# kulgurpowerproto2.net
KiCad netlist of a schematic drawn in EAGLE
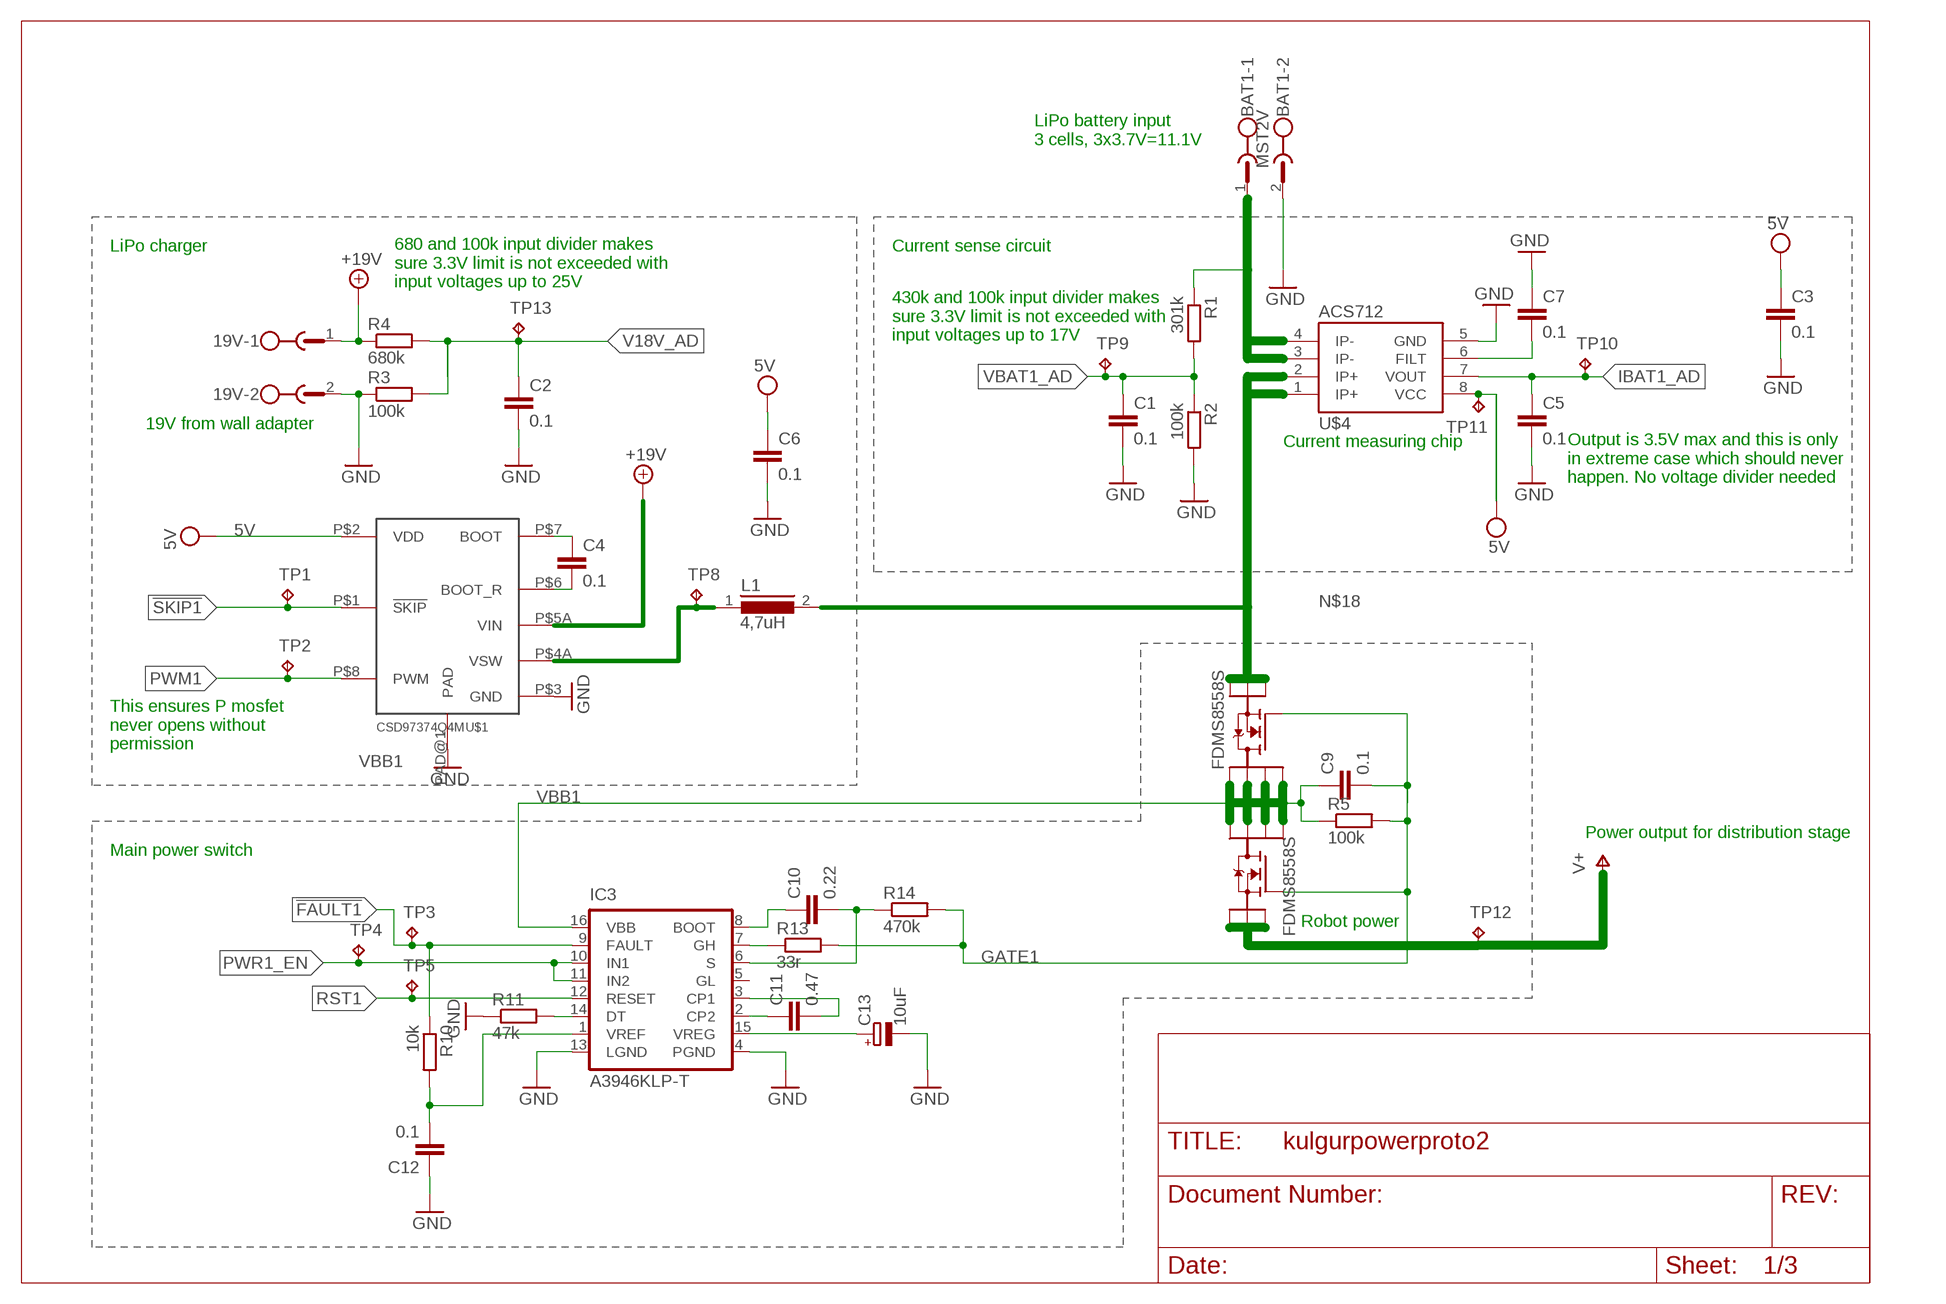
[diagram p0: schematic, sheet 1]
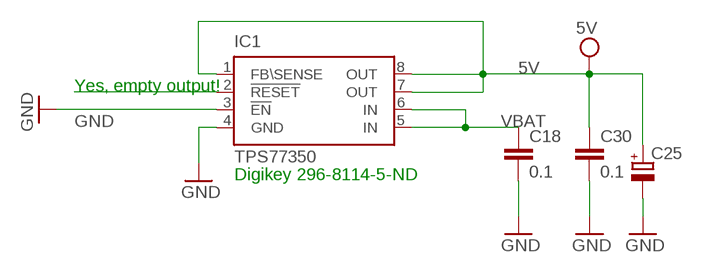
[diagram p1: schematic, sheet 2]
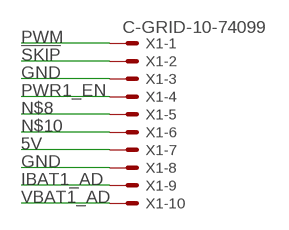
[diagram p2: schematic, sheet 3]

(export (version "E")
  (design (tool "Eeschema 10.0.6"))
  (components
    (comp (ref "C18")
      (value "0.1")
      (footprint "eagle-import:0603-CAP")
      (libsource (lib "eagle-import") (part "CAP0603-CAP"))
    )
    (comp (ref "C25")
      (value "CPOL-EUD/7343-31R")
      (footprint "eagle-import:D_7343-31R")
      (libsource (lib "eagle-import") (part "CPOL-EUD/7343-31R"))
    )
    (comp (ref "C30")
      (value "0.1")
      (footprint "eagle-import:0603-CAP")
      (libsource (lib "eagle-import") (part "CAP0603-CAP"))
    )
    (comp (ref "IC1")
      (value "TPS77350")
      (footprint "eagle-import:MSOP8")
      (libsource (lib "eagle-import") (part "TPS773"))
    )
    (comp (ref "X1")
      (value "C-GRID-10-74099")
      (footprint "eagle-import:74099-10")
      (libsource (lib "eagle-import") (part "C-GRID-10-74099"))
    )
    (comp (ref "19V")
      (value "MST2V")
      (footprint "eagle-import:MSTBV2")
      (fields (field (name "OC_FARNELL") "unknown") (field (name "OC_NEWARK") "unknown"))
      (libsource (lib "eagle-import") (part "MST2V"))
    )
    (comp (ref "BAT1")
      (value "MST2V")
      (footprint "eagle-import:MSTBV2")
      (fields (field (name "OC_FARNELL") "unknown") (field (name "OC_NEWARK") "unknown"))
      (libsource (lib "eagle-import") (part "MST2V"))
    )
    (comp (ref "C1")
      (value "0.1")
      (footprint "eagle-import:C0603")
      (libsource (lib "eagle-import") (part "C-EUC0603"))
    )
    (comp (ref "C2")
      (value "0.1")
      (footprint "eagle-import:C0603")
      (libsource (lib "eagle-import") (part "C-EUC0603"))
    )
    (comp (ref "C3")
      (value "0.1")
      (footprint "eagle-import:C0603")
      (libsource (lib "eagle-import") (part "C-EUC0603"))
    )
    (comp (ref "C4")
      (value "0.1")
      (footprint "eagle-import:C0603")
      (libsource (lib "eagle-import") (part "C-EUC0603"))
    )
    (comp (ref "C5")
      (value "0.1")
      (footprint "eagle-import:C0603")
      (libsource (lib "eagle-import") (part "C-EUC0603"))
    )
    (comp (ref "C6")
      (value "0.1")
      (footprint "eagle-import:C0603")
      (libsource (lib "eagle-import") (part "C-EUC0603"))
    )
    (comp (ref "C7")
      (value "0.1")
      (footprint "eagle-import:C0603")
      (libsource (lib "eagle-import") (part "C-EUC0603"))
    )
    (comp (ref "C9")
      (value "0.1")
      (footprint "eagle-import:C0603")
      (libsource (lib "eagle-import") (part "resistor_C-EUC0603"))
    )
    (comp (ref "C10")
      (value "0.22")
      (footprint "eagle-import:C0603")
      (libsource (lib "eagle-import") (part "resistor_C-EUC0603"))
    )
    (comp (ref "C11")
      (value "0.47")
      (footprint "eagle-import:C0603")
      (libsource (lib "eagle-import") (part "resistor_C-EUC0603"))
    )
    (comp (ref "C12")
      (value "0.1")
      (footprint "eagle-import:C0603")
      (libsource (lib "eagle-import") (part "resistor_C-EUC0603"))
    )
    (comp (ref "C13")
      (value "10uF")
      (footprint "eagle-import:A_3216-18R")
      (libsource (lib "eagle-import") (part "resistor_CPOL-EUA/3216-18R"))
    )
    (comp (ref "IC3")
      (value "A3946KLP-T")
      (footprint "eagle-import:TSSOP16E")
      (libsource (lib "eagle-import") (part "A3946KLP-T"))
    )
    (comp (ref "L1")
      (value "4,7uH")
      (footprint "eagle-import:DR73")
      (libsource (lib "eagle-import") (part "DR73"))
    )
    (comp (ref "R1")
      (value "301k")
      (footprint "eagle-import:R0603")
      (libsource (lib "eagle-import") (part "R-EU_R0603"))
    )
    (comp (ref "R2")
      (value "100k")
      (footprint "eagle-import:R0603")
      (libsource (lib "eagle-import") (part "R-EU_R0603"))
    )
    (comp (ref "R3")
      (value "100k")
      (footprint "eagle-import:R0603")
      (libsource (lib "eagle-import") (part "R-EU_R0603"))
    )
    (comp (ref "R4")
      (value "680k")
      (footprint "eagle-import:R0603")
      (libsource (lib "eagle-import") (part "R-EU_R0603"))
    )
    (comp (ref "R5")
      (value "100k")
      (footprint "eagle-import:R0603")
      (libsource (lib "eagle-import") (part "R-EU_R0603"))
    )
    (comp (ref "R10")
      (value "10k")
      (footprint "eagle-import:R0603")
      (libsource (lib "eagle-import") (part "R-EU_R0603"))
    )
    (comp (ref "R11")
      (value "47k")
      (footprint "eagle-import:R0603")
      (libsource (lib "eagle-import") (part "R-EU_R0603"))
    )
    (comp (ref "R13")
      (value "33r")
      (footprint "eagle-import:R0603")
      (libsource (lib "eagle-import") (part "R-EU_R0603"))
    )
    (comp (ref "R14")
      (value "470k")
      (footprint "eagle-import:R0603")
      (libsource (lib "eagle-import") (part "R-EU_R0603"))
    )
    (comp (ref "TP1")
      (value "TPB2,54")
      (footprint "eagle-import:B2,54")
      (libsource (lib "eagle-import") (part "TPB2,54"))
    )
    (comp (ref "TP2")
      (value "TPB2,54")
      (footprint "eagle-import:B2,54")
      (libsource (lib "eagle-import") (part "TPB2,54"))
    )
    (comp (ref "TP3")
      (value "TPB2,54")
      (footprint "eagle-import:B2,54")
      (libsource (lib "eagle-import") (part "TPB2,54"))
    )
    (comp (ref "TP4")
      (value "TPB2,54")
      (footprint "eagle-import:B2,54")
      (libsource (lib "eagle-import") (part "TPB2,54"))
    )
    (comp (ref "TP5")
      (value "TPB2,54")
      (footprint "eagle-import:B2,54")
      (libsource (lib "eagle-import") (part "TPB2,54"))
    )
    (comp (ref "TP8")
      (value "TPB2,54")
      (footprint "eagle-import:B2,54")
      (libsource (lib "eagle-import") (part "TPB2,54"))
    )
    (comp (ref "TP9")
      (value "TPB2,54")
      (footprint "eagle-import:B2,54")
      (libsource (lib "eagle-import") (part "TPB2,54"))
    )
    (comp (ref "TP10")
      (value "TPB2,54")
      (footprint "eagle-import:B2,54")
      (libsource (lib "eagle-import") (part "TPB2,54"))
    )
    (comp (ref "TP11")
      (value "TPB2,54")
      (footprint "eagle-import:B2,54")
      (libsource (lib "eagle-import") (part "TPB2,54"))
    )
    (comp (ref "TP12")
      (value "TPB2,54")
      (footprint "eagle-import:B2,54")
      (libsource (lib "eagle-import") (part "TPB2,54"))
    )
    (comp (ref "TP13")
      (value "TPB2,54")
      (footprint "eagle-import:B2,54")
      (libsource (lib "eagle-import") (part "TPB2,54"))
    )
    (comp (ref "U$1")
      (value "CSD97374Q4M")
      (footprint "eagle-import:CSD97374Q4M")
      (libsource (lib "eagle-import") (part "CSD97374Q4M"))
    )
    (comp (ref "U$2")
      (value "FDMS8558S")
      (footprint "eagle-import:POWER56")
      (libsource (lib "eagle-import") (part "FDMS8558S"))
    )
    (comp (ref "U$3")
      (value "FDMS8558S")
      (footprint "eagle-import:POWER56")
      (libsource (lib "eagle-import") (part "FDMS8558S"))
    )
    (comp (ref "U$4")
      (value "ACS712")
      (footprint "eagle-import:SO08")
      (libsource (lib "eagle-import") (part "ACS712"))
    )
  )
  (nets
    (net (code "1") (name "+19V") (class "Default")
      (node (ref "19V") (pin "1") (pinfunction "1_1") (pintype "passive"))
      (node (ref "R4") (pin "1") (pinfunction "1_1") (pintype "passive"))
      (node (ref "U$1") (pin "P$5A") (pinfunction "VIN_P$5A") (pintype "bidirectional"))
    )
    (net (code "2") (name "5V") (class "Default")
      (node (ref "C25") (pin "+") (pinfunction "+_+") (pintype "passive"))
      (node (ref "C3") (pin "1") (pinfunction "1_1") (pintype "passive"))
      (node (ref "C30") (pin "1") (pinfunction "1_1") (pintype "passive"))
      (node (ref "C6") (pin "1") (pinfunction "1_1") (pintype "passive"))
      (node (ref "IC1") (pin "1") (pinfunction "FB\\SENSE_1") (pintype "input"))
      (node (ref "IC1") (pin "7") (pinfunction "OUT_7") (pintype "output"))
      (node (ref "IC1") (pin "8") (pinfunction "OUT_8") (pintype "passive"))
      (node (ref "TP11") (pin "TP") (pinfunction "TP_TP") (pintype "input"))
      (node (ref "U$1") (pin "P$2") (pinfunction "VDD_P$2") (pintype "bidirectional"))
      (node (ref "U$4") (pin "8") (pinfunction "VCC_8") (pintype "bidirectional"))
      (node (ref "X1") (pin "7") (pinfunction "S_7") (pintype "passive"))
    )
    (net (code "3") (name "GATE1") (class "Default")
      (node (ref "C9") (pin "2") (pinfunction "2_2") (pintype "passive"))
      (node (ref "R13") (pin "2") (pinfunction "2_2") (pintype "passive"))
      (node (ref "R14") (pin "2") (pinfunction "2_2") (pintype "passive"))
      (node (ref "R5") (pin "2") (pinfunction "2_2") (pintype "passive"))
      (node (ref "U$2") (pin "P$4") (pinfunction "G_P$4") (pintype "passive"))
      (node (ref "U$3") (pin "P$4") (pinfunction "G_P$4") (pintype "passive"))
    )
    (net (code "4") (name "GND") (class "Default")
      (node (ref "19V") (pin "2") (pinfunction "1_2") (pintype "passive"))
      (node (ref "BAT1") (pin "2") (pinfunction "1_2") (pintype "passive"))
      (node (ref "C1") (pin "2") (pinfunction "2_2") (pintype "passive"))
      (node (ref "C12") (pin "1") (pinfunction "1_1") (pintype "passive"))
      (node (ref "C13") (pin "-") (pinfunction "-_-") (pintype "passive"))
      (node (ref "C18") (pin "2") (pinfunction "2_2") (pintype "passive"))
      (node (ref "C2") (pin "2") (pinfunction "2_2") (pintype "passive"))
      (node (ref "C25") (pin "-") (pinfunction "-_-") (pintype "passive"))
      (node (ref "C3") (pin "2") (pinfunction "2_2") (pintype "passive"))
      (node (ref "C30") (pin "2") (pinfunction "2_2") (pintype "passive"))
      (node (ref "C5") (pin "2") (pinfunction "2_2") (pintype "passive"))
      (node (ref "C6") (pin "2") (pinfunction "2_2") (pintype "passive"))
      (node (ref "C7") (pin "1") (pinfunction "1_1") (pintype "passive"))
      (node (ref "IC1") (pin "3") (pinfunction "~{EN}_3") (pintype "input"))
      (node (ref "IC1") (pin "4") (pinfunction "GND_4") (pintype "power_in"))
      (node (ref "IC3") (pin "13") (pinfunction "LGND_13") (pintype "power_in"))
      (node (ref "IC3") (pin "4") (pinfunction "PGND_4") (pintype "power_in"))
      (node (ref "R11") (pin "1") (pinfunction "1_1") (pintype "passive"))
      (node (ref "R2") (pin "2") (pinfunction "2_2") (pintype "passive"))
      (node (ref "R3") (pin "1") (pinfunction "1_1") (pintype "passive"))
      (node (ref "U$1") (pin "P$3") (pinfunction "GND_P$3") (pintype "bidirectional"))
      (node (ref "U$1") (pin "PAD@1") (pinfunction "PAD_PAD@1") (pintype "bidirectional"))
      (node (ref "U$4") (pin "5") (pinfunction "GND_5") (pintype "bidirectional"))
      (node (ref "X1") (pin "3") (pinfunction "S_3") (pintype "passive"))
      (node (ref "X1") (pin "8") (pinfunction "S_8") (pintype "passive"))
    )
    (net (code "5") (name "IBAT1_AD") (class "Default")
      (node (ref "C5") (pin "1") (pinfunction "1_1") (pintype "passive"))
      (node (ref "TP10") (pin "TP") (pinfunction "TP_TP") (pintype "input"))
      (node (ref "U$4") (pin "7") (pinfunction "VOUT_7") (pintype "bidirectional"))
      (node (ref "X1") (pin "9") (pinfunction "S_9") (pintype "passive"))
    )
    (net (code "6") (name "N$8") (class "Default")
      (node (ref "X1") (pin "5") (pinfunction "S_5") (pintype "passive"))
    )
    (net (code "7") (name "N$10") (class "Default")
      (node (ref "X1") (pin "6") (pinfunction "S_6") (pintype "passive"))
    )
    (net (code "8") (name "N$18") (class "Default")
      (node (ref "L1") (pin "2") (pinfunction "2_2") (pintype "passive"))
      (node (ref "U$2") (pin "P$1") (pinfunction "S1_P$1") (pintype "passive"))
      (node (ref "U$2") (pin "P$2") (pinfunction "S2_P$2") (pintype "passive"))
      (node (ref "U$2") (pin "P$3") (pinfunction "S3_P$3") (pintype "passive"))
      (node (ref "U$4") (pin "1") (pinfunction "IP+_1") (pintype "bidirectional"))
      (node (ref "U$4") (pin "2") (pinfunction "IP+_2") (pintype "bidirectional"))
    )
    (net (code "9") (name "Net-(BAT1-Pad1)") (class "Default")
      (node (ref "BAT1") (pin "1") (pinfunction "1_1") (pintype "passive"))
      (node (ref "R1") (pin "1") (pinfunction "1_1") (pintype "passive"))
      (node (ref "U$4") (pin "3") (pinfunction "IP-_3") (pintype "bidirectional"))
      (node (ref "U$4") (pin "4") (pinfunction "IP-_4") (pintype "bidirectional"))
    )
    (net (code "10") (name "Net-(IC3-BOOT)") (class "Default")
      (node (ref "C10") (pin "1") (pinfunction "1_1") (pintype "passive"))
      (node (ref "IC3") (pin "8") (pinfunction "BOOT_8") (pintype "input"))
    )
    (net (code "11") (name "Net-(IC3-CP1)") (class "Default")
      (node (ref "C11") (pin "2") (pinfunction "2_2") (pintype "passive"))
      (node (ref "IC3") (pin "3") (pinfunction "CP1_3") (pintype "passive"))
    )
    (net (code "12") (name "Net-(IC3-CP2)") (class "Default")
      (node (ref "C11") (pin "1") (pinfunction "1_1") (pintype "passive"))
      (node (ref "IC3") (pin "2") (pinfunction "CP2_2") (pintype "passive"))
    )
    (net (code "13") (name "Net-(IC3-DT)") (class "Default")
      (node (ref "IC3") (pin "14") (pinfunction "DT_14") (pintype "passive"))
      (node (ref "R11") (pin "2") (pinfunction "2_2") (pintype "passive"))
    )
    (net (code "14") (name "Net-(IC3-GH)") (class "Default")
      (node (ref "IC3") (pin "7") (pinfunction "GH_7") (pintype "output"))
      (node (ref "R13") (pin "1") (pinfunction "1_1") (pintype "passive"))
    )
    (net (code "15") (name "Net-(IC3-S)") (class "Default")
      (node (ref "C10") (pin "2") (pinfunction "2_2") (pintype "passive"))
      (node (ref "IC3") (pin "6") (pinfunction "S_6") (pintype "input"))
      (node (ref "R14") (pin "1") (pinfunction "1_1") (pintype "passive"))
    )
    (net (code "16") (name "Net-(IC3-VREF)") (class "Default")
      (node (ref "C12") (pin "2") (pinfunction "2_2") (pintype "passive"))
      (node (ref "IC3") (pin "1") (pinfunction "VREF_1") (pintype "passive"))
      (node (ref "R10") (pin "2") (pinfunction "2_2") (pintype "passive"))
    )
    (net (code "17") (name "Net-(IC3-VREG)") (class "Default")
      (node (ref "C13") (pin "+") (pinfunction "+_+") (pintype "passive"))
      (node (ref "IC3") (pin "15") (pinfunction "VREG_15") (pintype "passive"))
    )
    (net (code "18") (name "Net-(U$1-BOOT)") (class "Default")
      (node (ref "C4") (pin "1") (pinfunction "1_1") (pintype "passive"))
      (node (ref "U$1") (pin "P$7") (pinfunction "BOOT_P$7") (pintype "bidirectional"))
    )
    (net (code "19") (name "Net-(U$1-BOOT_R)") (class "Default")
      (node (ref "C4") (pin "2") (pinfunction "2_2") (pintype "passive"))
      (node (ref "U$1") (pin "P$6") (pinfunction "BOOT_R_P$6") (pintype "bidirectional"))
    )
    (net (code "20") (name "Net-(U$1-VSW)") (class "Default")
      (node (ref "L1") (pin "1") (pinfunction "1_1") (pintype "passive"))
      (node (ref "TP8") (pin "TP") (pinfunction "TP_TP") (pintype "input"))
      (node (ref "U$1") (pin "P$4A") (pinfunction "VSW_P$4A") (pintype "bidirectional"))
    )
    (net (code "21") (name "Net-(U$4-FILT)") (class "Default")
      (node (ref "C7") (pin "2") (pinfunction "2_2") (pintype "passive"))
      (node (ref "U$4") (pin "6") (pinfunction "FILT_6") (pintype "bidirectional"))
    )
    (net (code "22") (name "PWM") (class "Default")
      (node (ref "X1") (pin "1") (pinfunction "S_1") (pintype "passive"))
    )
    (net (code "23") (name "PWM1") (class "Default")
      (node (ref "TP2") (pin "TP") (pinfunction "TP_TP") (pintype "input"))
      (node (ref "U$1") (pin "P$8") (pinfunction "PWM_P$8") (pintype "bidirectional"))
    )
    (net (code "24") (name "PWR1_EN") (class "Default")
      (node (ref "IC3") (pin "10") (pinfunction "IN1_10") (pintype "input"))
      (node (ref "IC3") (pin "11") (pinfunction "IN2_11") (pintype "input"))
      (node (ref "TP4") (pin "TP") (pinfunction "TP_TP") (pintype "input"))
      (node (ref "X1") (pin "4") (pinfunction "S_4") (pintype "passive"))
    )
    (net (code "25") (name "RST1") (class "Default")
      (node (ref "IC3") (pin "12") (pinfunction "RESET_12") (pintype "input"))
      (node (ref "TP5") (pin "TP") (pinfunction "TP_TP") (pintype "input"))
    )
    (net (code "26") (name "V+") (class "Default")
      (node (ref "TP12") (pin "TP") (pinfunction "TP_TP") (pintype "input"))
      (node (ref "U$3") (pin "P$1") (pinfunction "S1_P$1") (pintype "passive"))
      (node (ref "U$3") (pin "P$2") (pinfunction "S2_P$2") (pintype "passive"))
      (node (ref "U$3") (pin "P$3") (pinfunction "S3_P$3") (pintype "passive"))
    )
    (net (code "27") (name "V18V_AD") (class "Default")
      (node (ref "C2") (pin "1") (pinfunction "1_1") (pintype "passive"))
      (node (ref "R3") (pin "2") (pinfunction "2_2") (pintype "passive"))
      (node (ref "R4") (pin "2") (pinfunction "2_2") (pintype "passive"))
      (node (ref "TP13") (pin "TP") (pinfunction "TP_TP") (pintype "input"))
    )
    (net (code "28") (name "VBAT") (class "Default")
      (node (ref "C18") (pin "1") (pinfunction "1_1") (pintype "passive"))
      (node (ref "IC1") (pin "5") (pinfunction "IN_5") (pintype "input"))
      (node (ref "IC1") (pin "6") (pinfunction "IN_6") (pintype "input"))
    )
    (net (code "29") (name "VBAT1_AD") (class "Default")
      (node (ref "C1") (pin "1") (pinfunction "1_1") (pintype "passive"))
      (node (ref "R1") (pin "2") (pinfunction "2_2") (pintype "passive"))
      (node (ref "R2") (pin "1") (pinfunction "1_1") (pintype "passive"))
      (node (ref "TP9") (pin "TP") (pinfunction "TP_TP") (pintype "input"))
      (node (ref "X1") (pin "10") (pinfunction "S_10") (pintype "passive"))
    )
    (net (code "30") (name "VBB1") (class "Default")
      (node (ref "C9") (pin "1") (pinfunction "1_1") (pintype "passive"))
      (node (ref "IC3") (pin "16") (pinfunction "VBB_16") (pintype "input"))
      (node (ref "R5") (pin "1") (pinfunction "1_1") (pintype "passive"))
      (node (ref "U$2") (pin "P$5") (pinfunction "D4_P$5") (pintype "passive"))
      (node (ref "U$2") (pin "P$6") (pinfunction "D3_P$6") (pintype "passive"))
      (node (ref "U$2") (pin "P$7") (pinfunction "D2_P$7") (pintype "passive"))
      (node (ref "U$2") (pin "P$8") (pinfunction "D1_P$8") (pintype "passive"))
      (node (ref "U$3") (pin "P$5") (pinfunction "D4_P$5") (pintype "passive"))
      (node (ref "U$3") (pin "P$6") (pinfunction "D3_P$6") (pintype "passive"))
      (node (ref "U$3") (pin "P$7") (pinfunction "D2_P$7") (pintype "passive"))
      (node (ref "U$3") (pin "P$8") (pinfunction "D1_P$8") (pintype "passive"))
    )
    (net (code "31") (name "unconnected-(IC1-~{RESET}-Pad2)") (class "Default")
      (node (ref "IC1") (pin "2") (pinfunction "~{RESET}_2") (pintype "input"))
    )
    (net (code "32") (name "unconnected-(IC3-GL-Pad5)") (class "Default")
      (node (ref "IC3") (pin "5") (pinfunction "GL_5") (pintype "output"))
    )
    (net (code "33") (name "~{FAULT1}") (class "Default")
      (node (ref "IC3") (pin "9") (pinfunction "FAULT_9") (pintype "output"))
      (node (ref "R10") (pin "1") (pinfunction "1_1") (pintype "passive"))
      (node (ref "TP3") (pin "TP") (pinfunction "TP_TP") (pintype "input"))
    )
    (net (code "34") (name "~{SKIP1}") (class "Default")
      (node (ref "TP1") (pin "TP") (pinfunction "TP_TP") (pintype "input"))
      (node (ref "U$1") (pin "P$1") (pinfunction "~{SKIP}_P$1") (pintype "bidirectional"))
    )
    (net (code "35") (name "~{SKIP}") (class "Default")
      (node (ref "X1") (pin "2") (pinfunction "S_2") (pintype "passive"))
    )
  )
)
